# HubBoard.net
KiCad netlist of a schematic drawn in Altium Designer
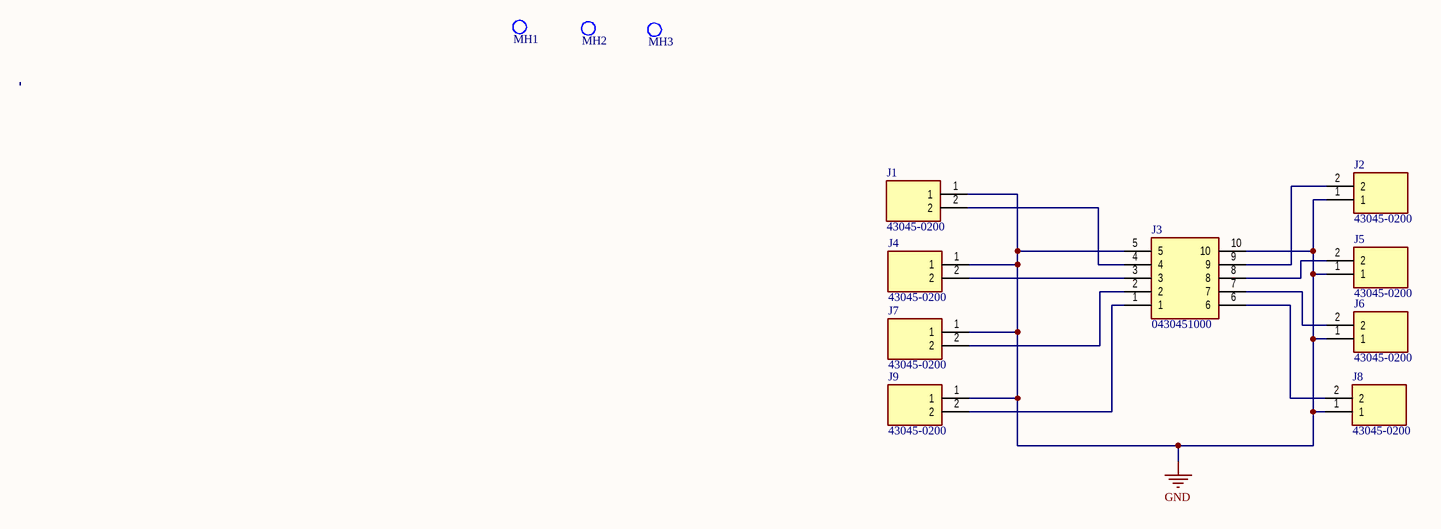
[diagram p0: HubBoard.SchDoc]

(export (version "E")
  (design (tool "Eeschema 10.0.6"))
  (components
    (comp (ref "J1")
      (value "43045-0200")
      (footprint "SamacSys:43045-0200")
      (description "Connector")
      (fields (field (name "MOUSER PART NUMBER") "538-43045-0200"))
      (libsource (lib "SamacSys") (part "43045-0200"))
    )
    (comp (ref "J2")
      (value "43045-0200")
      (footprint "SamacSys:43045-0200")
      (description "Connector")
      (fields (field (name "MOUSER PART NUMBER") "538-43045-0200"))
      (libsource (lib "") (part "43045-0200_1"))
    )
    (comp (ref "J3")
      (value "0430451000")
      (footprint "SamacSys:0430451000")
      (description "Connector")
      (libsource (lib "SamacSys") (part "0430451000"))
    )
    (comp (ref "J4")
      (value "43045-0200")
      (footprint "SamacSys:43045-0200")
      (description "Connector")
      (fields (field (name "MOUSER PART NUMBER") "538-43045-0200"))
      (libsource (lib "SamacSys") (part "43045-0200"))
    )
    (comp (ref "J5")
      (value "43045-0200")
      (footprint "SamacSys:43045-0200")
      (description "Connector")
      (fields (field (name "MOUSER PART NUMBER") "538-43045-0200"))
      (libsource (lib "") (part "43045-0200_1"))
    )
    (comp (ref "J6")
      (value "43045-0200")
      (footprint "SamacSys:43045-0200")
      (description "Connector")
      (fields (field (name "MOUSER PART NUMBER") "538-43045-0200"))
      (libsource (lib "") (part "43045-0200_1"))
    )
    (comp (ref "J7")
      (value "43045-0200")
      (footprint "SamacSys:43045-0200")
      (description "Connector")
      (fields (field (name "MOUSER PART NUMBER") "538-43045-0200"))
      (libsource (lib "SamacSys") (part "43045-0200"))
    )
    (comp (ref "J8")
      (value "43045-0200")
      (footprint "SamacSys:43045-0200")
      (description "Connector")
      (fields (field (name "MOUSER PART NUMBER") "538-43045-0200"))
      (libsource (lib "") (part "43045-0200_1"))
    )
    (comp (ref "J9")
      (value "43045-0200")
      (footprint "SamacSys:43045-0200")
      (description "Connector")
      (fields (field (name "MOUSER PART NUMBER") "538-43045-0200"))
      (libsource (lib "SamacSys") (part "43045-0200"))
    )
    (comp (ref "MH1")
      (value "Mounting Hole")
      (footprint "MOUNT-HOLE")
      (description "#4 Screw, 0.116in Diameter")
      (libsource (lib "SOARSchematics") (part "Mounting Hole"))
    )
    (comp (ref "MH2")
      (value "Mounting Hole")
      (footprint "MOUNT-HOLE")
      (description "#4 Screw, 0.116in Diameter")
      (libsource (lib "SOARSchematics") (part "Mounting Hole"))
    )
    (comp (ref "MH3")
      (value "Mounting Hole")
      (footprint "MOUNT-HOLE")
      (description "#4 Screw, 0.116in Diameter")
      (libsource (lib "SOARSchematics") (part "Mounting Hole"))
    )
  )
  (nets
    (net (code "1") (name "GND") (class "Default")
      (node (ref "J1") (pin "1") (pinfunction "1_1") (pintype "passive"))
      (node (ref "J2") (pin "1") (pinfunction "1_1") (pintype "passive"))
      (node (ref "J3") (pin "10") (pinfunction "10_10") (pintype "passive"))
      (node (ref "J3") (pin "5") (pinfunction "5_5") (pintype "passive"))
      (node (ref "J4") (pin "1") (pinfunction "1_1") (pintype "passive"))
      (node (ref "J5") (pin "1") (pinfunction "1_1") (pintype "passive"))
      (node (ref "J6") (pin "1") (pinfunction "1_1") (pintype "passive"))
      (node (ref "J7") (pin "1") (pinfunction "1_1") (pintype "passive"))
      (node (ref "J8") (pin "1") (pinfunction "1_1") (pintype "passive"))
      (node (ref "J9") (pin "1") (pinfunction "1_1") (pintype "passive"))
    )
    (net (code "2") (name "Net-(J1-Pad2)") (class "Default")
      (node (ref "J1") (pin "2") (pinfunction "2_2") (pintype "passive"))
      (node (ref "J3") (pin "4") (pinfunction "4_4") (pintype "passive"))
    )
    (net (code "3") (name "Net-(J2-Pad2)") (class "Default")
      (node (ref "J2") (pin "2") (pinfunction "2_2") (pintype "passive"))
      (node (ref "J3") (pin "9") (pinfunction "9_9") (pintype "passive"))
    )
    (net (code "4") (name "Net-(J3-Pad1)") (class "Default")
      (node (ref "J3") (pin "1") (pinfunction "1_1") (pintype "passive"))
      (node (ref "J9") (pin "2") (pinfunction "2_2") (pintype "passive"))
    )
    (net (code "5") (name "Net-(J3-Pad2)") (class "Default")
      (node (ref "J3") (pin "2") (pinfunction "2_2") (pintype "passive"))
      (node (ref "J7") (pin "2") (pinfunction "2_2") (pintype "passive"))
    )
    (net (code "6") (name "Net-(J3-Pad3)") (class "Default")
      (node (ref "J3") (pin "3") (pinfunction "3_3") (pintype "passive"))
      (node (ref "J4") (pin "2") (pinfunction "2_2") (pintype "passive"))
    )
    (net (code "7") (name "Net-(J3-Pad6)") (class "Default")
      (node (ref "J3") (pin "6") (pinfunction "6_6") (pintype "passive"))
      (node (ref "J8") (pin "2") (pinfunction "2_2") (pintype "passive"))
    )
    (net (code "8") (name "Net-(J3-Pad7)") (class "Default")
      (node (ref "J3") (pin "7") (pinfunction "7_7") (pintype "passive"))
      (node (ref "J6") (pin "2") (pinfunction "2_2") (pintype "passive"))
    )
    (net (code "9") (name "Net-(J3-Pad8)") (class "Default")
      (node (ref "J3") (pin "8") (pinfunction "8_8") (pintype "passive"))
      (node (ref "J5") (pin "2") (pinfunction "2_2") (pintype "passive"))
    )
  )
)
